# Connector.net
KiCad netlist of a schematic drawn in Altium Designer
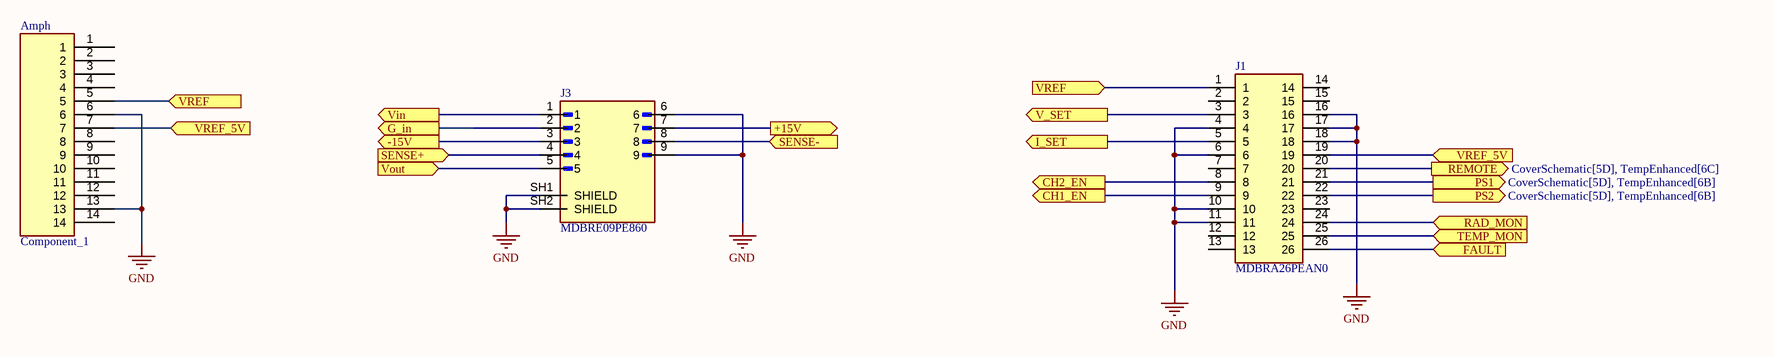
[diagram p0: Connector.SchDoc]

(export (version "E")
  (design (tool "Eeschema 10.0.6"))
  (components
    (comp (ref "Amph")
      (value "Component_1")
      (footprint "PCBComponent_1")
      (libsource (lib "ACRK-16-01-G-T-B1-M-1") (part "ACRK-16-01-G-T-B1-M-1"))
    )
    (comp (ref "J1")
      (value "MDBRA26PEAN0")
      (footprint "SamacSys:MDBRA26PEAN0")
      (description "Connector")
      (fields (field (name "MOUSER PART NUMBER") "523-MDBRA26PEAN0"))
      (libsource (lib "*") (part "MDBRA26PEAN0"))
    )
    (comp (ref "J3")
      (value "MDBRE09PE860")
      (footprint "MDBRE09PE860:AMPHENOL_MDBRE09PE860")
      (fields (field (name "MF") "{'manufacturer': u'Amphenol Commercial Products'}"))
      (libsource (lib "MDBRE09PE860") (part "MDBRE09PE860"))
    )
  )
  (nets
    (net (code "1") (name "/+15V") (class "Default")
      (node (ref "J3") (pin "7") (pinfunction "7_7") (pintype "passive"))
    )
    (net (code "2") (name "/-15V") (class "Default")
      (node (ref "J3") (pin "3") (pinfunction "3_3") (pintype "passive"))
    )
    (net (code "3") (name "/CH1_EN") (class "Default")
      (node (ref "J1") (pin "9") (pinfunction "9_9") (pintype "passive"))
    )
    (net (code "4") (name "/CH2_EN") (class "Default")
      (node (ref "J1") (pin "8") (pinfunction "8_8") (pintype "passive"))
    )
    (net (code "5") (name "/FAULT") (class "Default")
      (node (ref "J1") (pin "26") (pinfunction "26_26") (pintype "passive"))
    )
    (net (code "6") (name "/G_in") (class "Default")
      (node (ref "J3") (pin "2") (pinfunction "2_2") (pintype "passive"))
    )
    (net (code "7") (name "/I_SET") (class "Default")
      (node (ref "J1") (pin "5") (pinfunction "5_5") (pintype "passive"))
    )
    (net (code "8") (name "/PS1") (class "Default")
      (node (ref "J1") (pin "21") (pinfunction "21_21") (pintype "passive"))
    )
    (net (code "9") (name "/PS2") (class "Default")
      (node (ref "J1") (pin "22") (pinfunction "22_22") (pintype "passive"))
    )
    (net (code "10") (name "/RAD_MON") (class "Default")
      (node (ref "J1") (pin "24") (pinfunction "24_24") (pintype "passive"))
    )
    (net (code "11") (name "/REMOTE") (class "Default")
      (node (ref "J1") (pin "20") (pinfunction "20_20") (pintype "passive"))
    )
    (net (code "12") (name "/SENSE+") (class "Default")
      (node (ref "J3") (pin "4") (pinfunction "4_4") (pintype "passive"))
    )
    (net (code "13") (name "/SENSE-") (class "Default")
      (node (ref "J3") (pin "8") (pinfunction "8_8") (pintype "passive"))
    )
    (net (code "14") (name "/TEMP_MON") (class "Default")
      (node (ref "J1") (pin "25") (pinfunction "25_25") (pintype "passive"))
    )
    (net (code "15") (name "/VREF") (class "Default")
      (node (ref "Amph") (pin "5") (pinfunction "5_5") (pintype "passive"))
      (node (ref "J1") (pin "1") (pinfunction "1_1") (pintype "passive"))
    )
    (net (code "16") (name "/VREF_5V") (class "Default")
      (node (ref "Amph") (pin "7") (pinfunction "7_7") (pintype "passive"))
      (node (ref "J1") (pin "19") (pinfunction "19_19") (pintype "passive"))
    )
    (net (code "17") (name "/V_SET") (class "Default")
      (node (ref "J1") (pin "3") (pinfunction "3_3") (pintype "passive"))
    )
    (net (code "18") (name "/Vin") (class "Default")
      (node (ref "J3") (pin "1") (pinfunction "1_1") (pintype "passive"))
    )
    (net (code "19") (name "/Vout") (class "Default")
      (node (ref "J3") (pin "5") (pinfunction "5_5") (pintype "passive"))
    )
    (net (code "20") (name "GND") (class "Default")
      (node (ref "Amph") (pin "13") (pinfunction "13_13") (pintype "passive"))
      (node (ref "Amph") (pin "6") (pinfunction "6_6") (pintype "passive"))
      (node (ref "J1") (pin "10") (pinfunction "10_10") (pintype "passive"))
      (node (ref "J1") (pin "11") (pinfunction "11_11") (pintype "passive"))
      (node (ref "J1") (pin "16") (pinfunction "16_16") (pintype "passive"))
      (node (ref "J1") (pin "17") (pinfunction "17_17") (pintype "passive"))
      (node (ref "J1") (pin "18") (pinfunction "18_18") (pintype "passive"))
      (node (ref "J1") (pin "4") (pinfunction "4_4") (pintype "passive"))
      (node (ref "J1") (pin "6") (pinfunction "6_6") (pintype "passive"))
      (node (ref "J3") (pin "6") (pinfunction "6_6") (pintype "passive"))
      (node (ref "J3") (pin "9") (pinfunction "9_9") (pintype "passive"))
      (node (ref "J3") (pin "SH1") (pinfunction "SHIELD_SH1") (pintype "passive"))
      (node (ref "J3") (pin "SH2") (pinfunction "SHIELD_SH2") (pintype "passive"))
    )
    (net (code "21") (name "unconnected-(Amph-Pad1)") (class "Default")
      (node (ref "Amph") (pin "1") (pinfunction "1_1") (pintype "passive"))
    )
    (net (code "22") (name "unconnected-(Amph-Pad2)") (class "Default")
      (node (ref "Amph") (pin "2") (pinfunction "2_2") (pintype "passive"))
    )
    (net (code "23") (name "unconnected-(Amph-Pad3)") (class "Default")
      (node (ref "Amph") (pin "3") (pinfunction "3_3") (pintype "passive"))
    )
    (net (code "24") (name "unconnected-(Amph-Pad4)") (class "Default")
      (node (ref "Amph") (pin "4") (pinfunction "4_4") (pintype "passive"))
    )
    (net (code "25") (name "unconnected-(Amph-Pad8)") (class "Default")
      (node (ref "Amph") (pin "8") (pinfunction "8_8") (pintype "passive"))
    )
    (net (code "26") (name "unconnected-(Amph-Pad9)") (class "Default")
      (node (ref "Amph") (pin "9") (pinfunction "9_9") (pintype "passive"))
    )
    (net (code "27") (name "unconnected-(Amph-Pad10)") (class "Default")
      (node (ref "Amph") (pin "10") (pinfunction "10_10") (pintype "passive"))
    )
    (net (code "28") (name "unconnected-(Amph-Pad11)") (class "Default")
      (node (ref "Amph") (pin "11") (pinfunction "11_11") (pintype "passive"))
    )
    (net (code "29") (name "unconnected-(Amph-Pad12)") (class "Default")
      (node (ref "Amph") (pin "12") (pinfunction "12_12") (pintype "passive"))
    )
    (net (code "30") (name "unconnected-(Amph-Pad14)") (class "Default")
      (node (ref "Amph") (pin "14") (pinfunction "14_14") (pintype "passive"))
    )
    (net (code "31") (name "unconnected-(J1-Pad2)") (class "Default")
      (node (ref "J1") (pin "2") (pinfunction "2_2") (pintype "passive"))
    )
    (net (code "32") (name "unconnected-(J1-Pad7)") (class "Default")
      (node (ref "J1") (pin "7") (pinfunction "7_7") (pintype "passive"))
    )
    (net (code "33") (name "unconnected-(J1-Pad12)") (class "Default")
      (node (ref "J1") (pin "12") (pinfunction "12_12") (pintype "passive"))
    )
    (net (code "34") (name "unconnected-(J1-Pad13)") (class "Default")
      (node (ref "J1") (pin "13") (pinfunction "13_13") (pintype "passive"))
    )
    (net (code "35") (name "unconnected-(J1-Pad14)") (class "Default")
      (node (ref "J1") (pin "14") (pinfunction "14_14") (pintype "passive"))
    )
    (net (code "36") (name "unconnected-(J1-Pad15)") (class "Default")
      (node (ref "J1") (pin "15") (pinfunction "15_15") (pintype "passive"))
    )
    (net (code "37") (name "unconnected-(J1-Pad23)") (class "Default")
      (node (ref "J1") (pin "23") (pinfunction "23_23") (pintype "passive"))
    )
  )
)
